# M1-Test-Board.net
KiCad netlist of a schematic drawn in Altium Designer
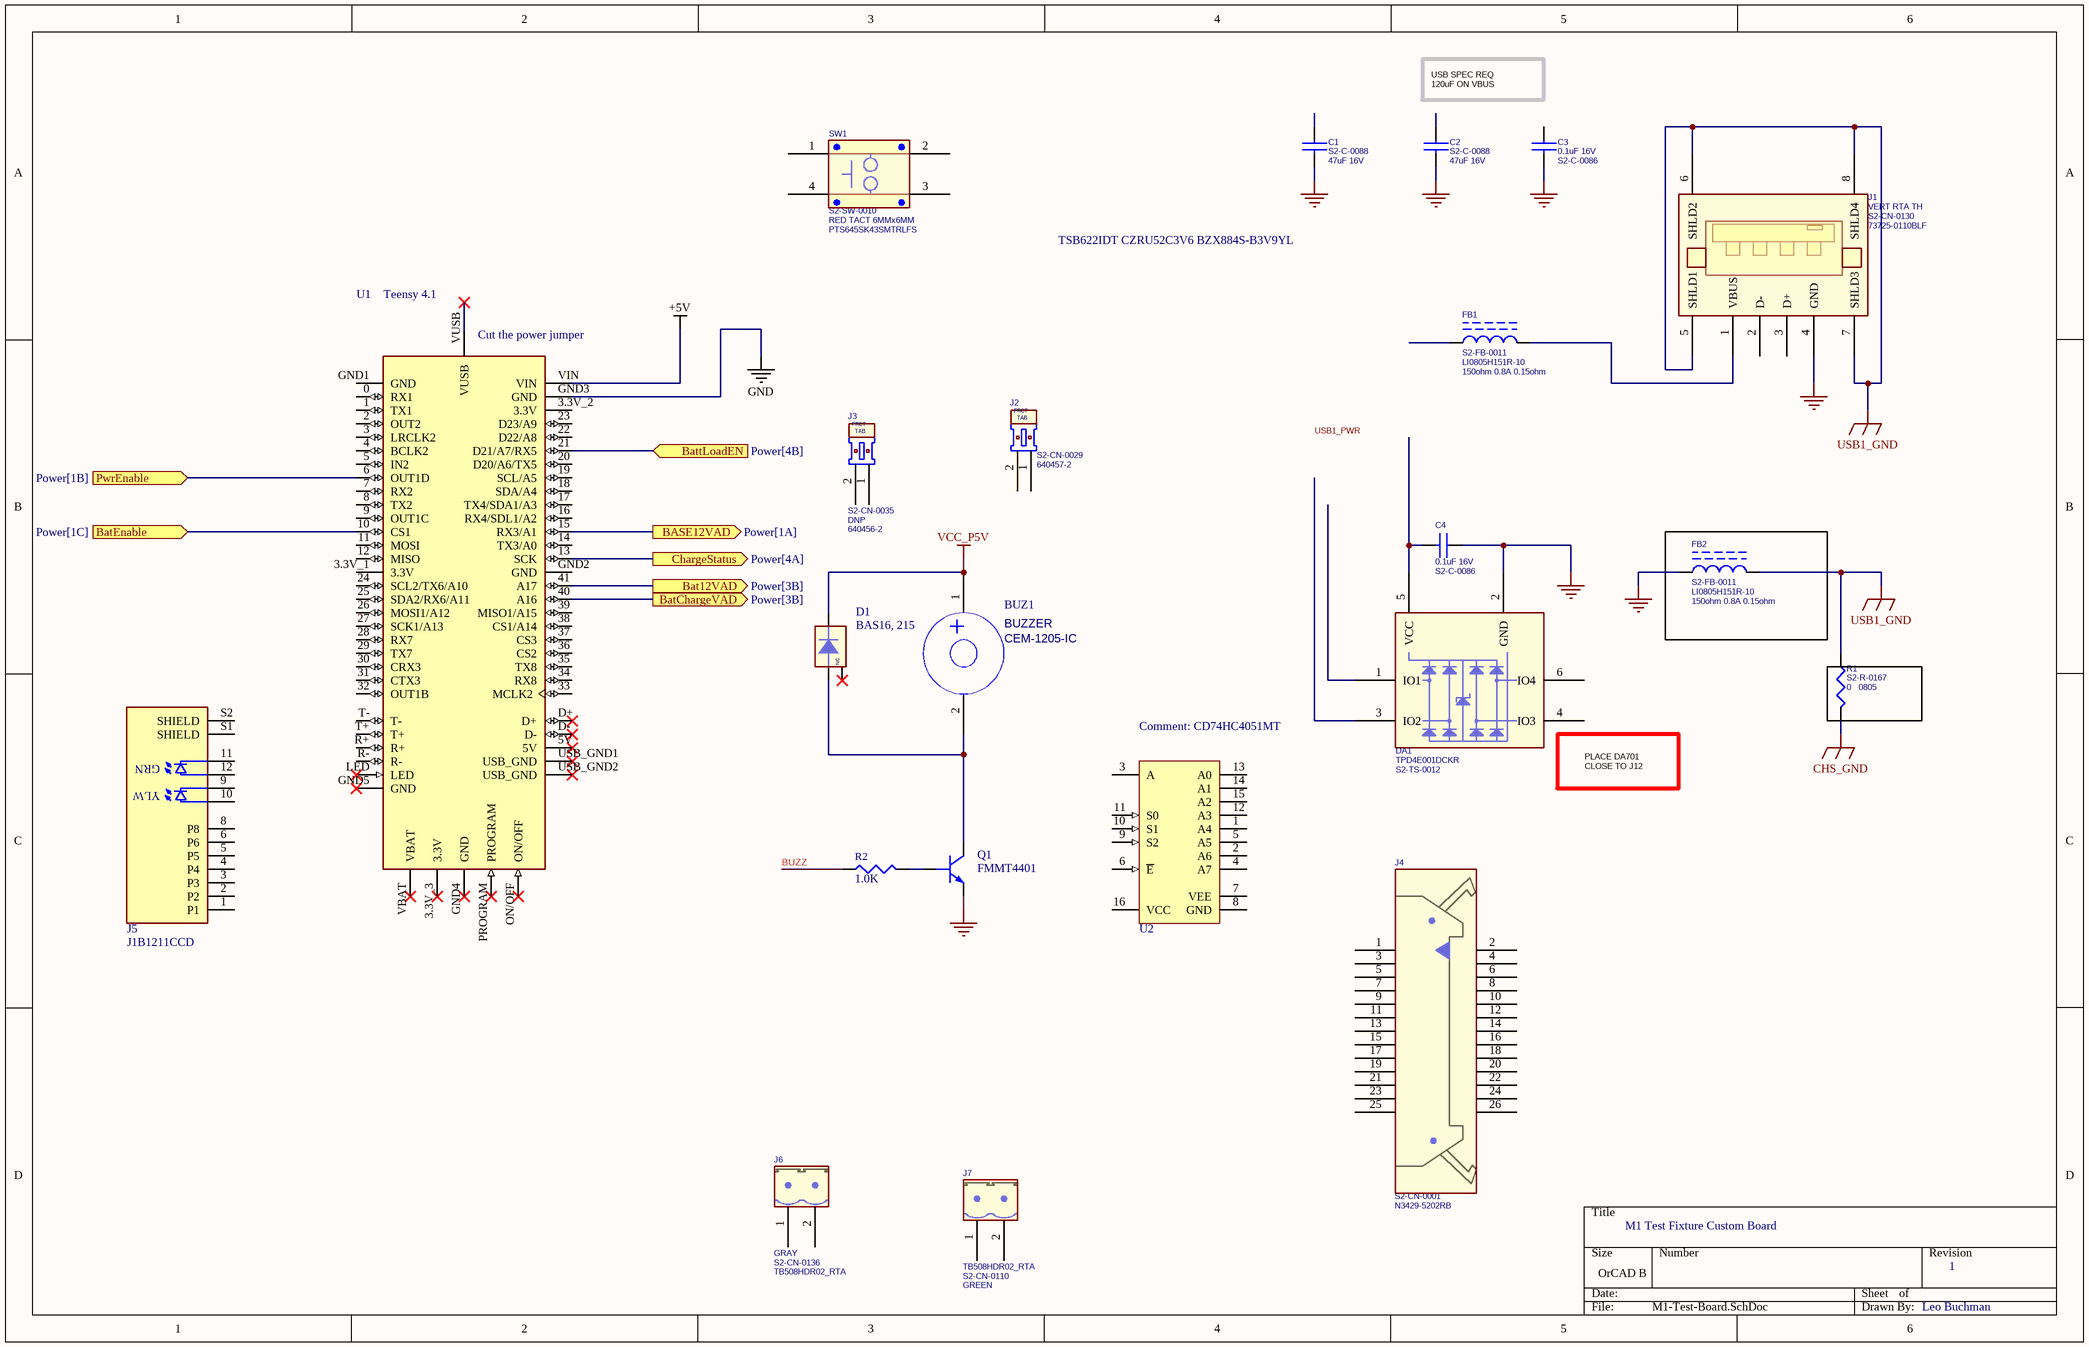
[diagram p0: M1-Test-Board.SchDoc]

(export (version "E")
  (design (tool "Eeschema 10.0.6"))
  (components
    (comp (ref "BUZ1")
      (value "BUZZER")
      (footprint "BUZZ-MB5120C")
      (description "BUZZER MAGNETIC INDICATOR, INTERNAL DRIVE 2.3KHz 12MM DIAMETER 7.6MM LEAD SPACING")
      (fields
        (field (name "PACKAGE") "CEM-1205-IC")
        (field (name "ADI PART NUMBER") "3716-0001")
        (field (name "VOLTAGE") "5V")
      )
      (libsource (lib "SAM_REV_D") (part "S2-BZ-0001"))
    )
    (comp (ref "C1")
      (value "C_47U_16V_1210")
      (footprint "CAPC3225X270N")
      (fields (field (name "S2_PN") "S2-C-0088") (field (name "DESC") "47uF 16V"))
      (libsource (lib "NODE_V2") (part "C_47U_16V_1210"))
    )
    (comp (ref "C2")
      (value "C_47U_16V_1210")
      (footprint "CAPC3225X270N")
      (fields (field (name "S2_PN") "S2-C-0088") (field (name "DESC") "47uF 16V"))
      (libsource (lib "NODE_V2") (part "C_47U_16V_1210"))
    )
    (comp (ref "C3")
      (value "C_0U1_16V_0402")
      (footprint "CAPC1005X55N")
      (fields (field (name "DESC") "0.1uF 16V") (field (name "S2_PN") "S2-C-0086"))
      (libsource (lib "NODE_V2") (part "C_0U1_16V_0402"))
    )
    (comp (ref "C4")
      (value "C_0U1_16V_0402")
      (footprint "CAPC1005X55N")
      (fields (field (name "DESC") "0.1uF 16V") (field (name "S2_PN") "S2-C-0086"))
      (libsource (lib "NODE_V2") (part "C_0U1_16V_0402"))
    )
    (comp (ref "D1")
      (value "BAS16, 215")
      (footprint "SAM_REV_D:SOT23-3")
      (description "DIODE SWITCHING 500nA REVERSE LEAKAGE SOT-23-3")
      (fields (field (name "JLCPCB_PART") "C79997"))
      (libsource (lib "SAM_REV_D") (part "S2-D-0024"))
    )
    (comp (ref "DA1")
      (value "DA_TPD4E001_ESD_QUAD")
      (footprint "SOIC65Px210X110P-6N")
      (fields (field (name "DESC") "TPD4E001DCKR") (field (name "S2_PN") "S2-TS-0012"))
      (libsource (lib "NODE_V2") (part "DA_TPD4E001_ESD_QUAD"))
    )
    (comp (ref "FB1")
      (value "FB_0A8_150OHM_0805_DC_150mOHM")
      (footprint "FB0805")
      (fields
        (field (name "S2_PN") "S2-FB-0011")
        (field (name "DESC") "LI0805H151R-10")
        (field (name "ATTR2") "150ohm 0.8A 0.15ohm")
      )
      (libsource (lib "NODE_V2") (part "FB_0A8_150OHM_0805_DC_150mOHM"))
    )
    (comp (ref "FB2")
      (value "FB_0A8_150OHM_0805_DC_150mOHM")
      (footprint "FB0805")
      (fields
        (field (name "S2_PN") "S2-FB-0011")
        (field (name "DESC") "LI0805H151R-10")
        (field (name "ATTR2") "150ohm 0.8A 0.15ohm")
      )
      (libsource (lib "NODE_V2") (part "FB_0A8_150OHM_0805_DC_150mOHM"))
    )
    (comp (ref "J1")
      (value "CN_USB_TYPE_A_RTA_VERT_TH")
      (footprint "CONN_73725-0110BLF")
      (fields
        (field (name "ATTR2") "VERT RTA TH")
        (field (name "S2_PN") "S2-CN-0130")
        (field (name "DESC") "73725-0110BLF")
      )
      (libsource (lib "NODE_V2_M1") (part "CN_USB_TYPE_A_RTA_VERT_TH"))
    )
    (comp (ref "J2")
      (value "CN_100_2POS_RTA_FRICT_LOCK")
      (footprint "CONN_640457-2")
      (fields (field (name "S2_PN") "S2-CN-0029") (field (name "DESC") "640457-2"))
      (libsource (lib "NODE_V2_M1") (part "CN_100_2POS_RTA_FRICT_LOCK"))
    )
    (comp (ref "J3")
      (value "CN_100_2POS_STR_FRICT_LOCK")
      (footprint "Conn_640456-2")
      (fields (field (name "S2_PN") "S2-CN-0035") (field (name "DNP") "DNP") (field (name "DESC") "640456-2"))
      (libsource (lib "NODE_V2_M1") (part "CN_100_2POS_STR_FRICT_LOCK"))
    )
    (comp (ref "J4")
      (value "CN_100_26POS_13x2_RTA_LATCH")
      (footprint "CONN_N3429-5202RB")
      (fields (field (name "S2_PN") "S2-CN-0001") (field (name "DESC") "N3429-5202RB"))
      (libsource (lib "NODE_V2_M1") (part "CN_100_26POS_13x2_RTA_LATCH"))
    )
    (comp (ref "J5")
      (value "J1B1211CCD")
      (footprint "RJ45-TH_J1B1211CCD-EasyEda")
      (description "Single RJ45 Connector Module with 10/100 BASE")
      (fields (field (name "MANUFACTURER") "WIZnet") (field (name "LCSC PART NUMBER") "C910371"))
      (libsource (lib "Leo-Home-SQL-Lib") (part "SI-60182-F"))
    )
    (comp (ref "J6")
      (value "CN_5MM08_02POS_HEADER_RTA_GRAY")
      (footprint "Conn_5433668")
      (fields
        (field (name "ATTR2") "GRAY")
        (field (name "S2_PN") "S2-CN-0136")
        (field (name "DESC") "TB508HDR02_RTA")
      )
      (libsource (lib "NODE_V2_M1") (part "CN_5MM08_02POS_HEADER_RTA_GRAY"))
    )
    (comp (ref "J7")
      (value "CN_5MM08_02POS_HEADER_RTA_GRN")
      (footprint "Conn_5442002")
      (fields
        (field (name "DESC") "TB508HDR02_RTA")
        (field (name "S2_PN") "S2-CN-0110")
        (field (name "ATTR2") "GREEN")
      )
      (libsource (lib "NODE_V2_M1") (part "CN_5MM08_02POS_HEADER_RTA_GRN"))
    )
    (comp (ref "Q1")
      (value "FMMT4401")
      (footprint "SOT23-3")
      (description "TRANSISTOR NPN GEN PUR SOT-23")
      (fields (field (name "JLCPCB_PART") "C20526"))
      (libsource (lib "SAM_REV_D") (part "S2-Q-0005"))
    )
    (comp (ref "R1")
      (value "R_0_0805")
      (footprint "RESC2012X50N")
      (fields (field (name "S2_PN") "S2-R-0167") (field (name "DESC") "0   0805"))
      (libsource (lib "NODE_V2") (part "R_0_0805"))
    )
    (comp (ref "R2")
      (value "1.0K")
      (footprint "r0402")
      (description "RES 1K OHM 1/16W 1% 0402")
      (fields (field (name "JLCPCB_PART") "C21190"))
      (libsource (lib "SAM_REV_D") (part "S2-R-0157"))
    )
    (comp (ref "SW1")
      (value "SW_PTS645_SMT_RED")
      (footprint "SW_PTS645SK43SMTRLFS")
      (fields
        (field (name "S2_PN") "S2-SW-0010")
        (field (name "ATTR") "RED TACT 6MMx6MM")
        (field (name "DESC") "PTS645SK43SMTRLFS")
      )
      (libsource (lib "NODE_V2_M1") (part "SW_PTS645_SMT_RED"))
    )
    (comp (ref "U1")
      (value "Teensy 4.1")
      (footprint "MODULE_DEV-16771")
      (description "RT1062 Teensy 4.1 series ARM® Cortex®-M7 MPU")
      (fields (field (name "MANUFACTURER") "SparkFun") (field (name "MANUFACTURER PART NUMBER") "16771"))
      (libsource (lib "Leo-Home-SQL-Lib") (part "DEV-16771"))
    )
    (comp (ref "U2")
      (value "CD74HC4051MT")
      (footprint "D0016A_N")
      (description "High Speed CMOS 8-Channel Analog Multiplexer/Demultiplexer, D0016A, SMALL T&R")
      (fields
        (field (name "GENERIC PART NUMBER") "CD74HC4051")
        (field (name "MANUFACTURER") "Texas Instruments")
      )
      (libsource (lib "Altium Content Vault") (part "TI-CD74HCX4051-16"))
    )
  )
  (nets
    (net (code "1") (name "+5V") (class "Default")
      (node (ref "U1") (pin "VIN") (pinfunction "VIN_VIN") (pintype "power_in"))
    )
    (net (code "2") (name "/BASE12VAD") (class "Default")
      (node (ref "U1") (pin "15") (pinfunction "RX3/A1_15") (pintype "bidirectional"))
    )
    (net (code "3") (name "/BUZZ") (class "Default")
      (node (ref "R2") (pin "1") (pinfunction "1_1") (pintype "passive"))
    )
    (net (code "4") (name "/Bat12VAD") (class "Default")
      (node (ref "U1") (pin "41") (pinfunction "A17_41") (pintype "bidirectional"))
    )
    (net (code "5") (name "/BatChargeVAD") (class "Default")
      (node (ref "U1") (pin "40") (pinfunction "A16_40") (pintype "bidirectional"))
    )
    (net (code "6") (name "/BatEnable") (class "Default")
      (node (ref "U1") (pin "10") (pinfunction "CS1_10") (pintype "bidirectional"))
    )
    (net (code "7") (name "/BattLoadEN") (class "Default")
      (node (ref "U1") (pin "21") (pinfunction "D21/A7/RX5_21") (pintype "bidirectional"))
    )
    (net (code "8") (name "/ChargeStatus") (class "Default")
      (node (ref "U1") (pin "13") (pinfunction "SCK_13") (pintype "bidirectional"))
    )
    (net (code "9") (name "/PwrEnable") (class "Default")
      (node (ref "U1") (pin "6") (pinfunction "OUT1D_6") (pintype "bidirectional"))
    )
    (net (code "11") (name "CHS_GND") (class "Default")
      (node (ref "R1") (pin "2") (pinfunction "2_2") (pintype "passive"))
    )
    (net (code "12") (name "GND") (class "Default")
      (node (ref "C1") (pin "2") (pinfunction "2_2") (pintype "passive"))
      (node (ref "C2") (pin "2") (pinfunction "2_2") (pintype "passive"))
      (node (ref "C3") (pin "2") (pinfunction "2_2") (pintype "passive"))
      (node (ref "C4") (pin "1") (pinfunction "1_1") (pintype "passive"))
      (node (ref "DA1") (pin "2") (pinfunction "GND_2") (pintype "passive"))
      (node (ref "FB2") (pin "1") (pinfunction "1_1") (pintype "passive"))
      (node (ref "J1") (pin "4") (pinfunction "GND_4") (pintype "passive"))
      (node (ref "Q1") (pin "2") (pinfunction "E_2") (pintype "passive"))
      (node (ref "U1") (pin "GND3") (pinfunction "GND_GND3") (pintype "power_in"))
    )
    (net (code "13") (name "Net-(BUZ1-NEG)") (class "Default")
      (node (ref "BUZ1") (pin "2") (pinfunction "NEG_2") (pintype "power_in"))
      (node (ref "D1") (pin "1") (pinfunction "A_1") (pintype "passive"))
      (node (ref "Q1") (pin "1") (pinfunction "C_1") (pintype "passive"))
    )
    (net (code "14") (name "Net-(DA1-VCC)") (class "Default")
      (node (ref "C4") (pin "2") (pinfunction "2_2") (pintype "passive"))
      (node (ref "DA1") (pin "5") (pinfunction "VCC_5") (pintype "passive"))
    )
    (net (code "15") (name "Net-(J1-VBUS)") (class "Default")
      (node (ref "FB1") (pin "2") (pinfunction "2_2") (pintype "passive"))
      (node (ref "J1") (pin "1") (pinfunction "VBUS_1") (pintype "passive"))
    )
    (net (code "16") (name "Net-(Q1-B)") (class "Default")
      (node (ref "Q1") (pin "3") (pinfunction "B_3") (pintype "passive"))
      (node (ref "R2") (pin "2") (pinfunction "2_2") (pintype "passive"))
    )
    (net (code "17") (name "USB1_GND") (class "Default")
      (node (ref "FB2") (pin "2") (pinfunction "2_2") (pintype "passive"))
      (node (ref "J1") (pin "5") (pinfunction "SHLD1_5") (pintype "passive"))
      (node (ref "J1") (pin "6") (pinfunction "SHLD2_6") (pintype "passive"))
      (node (ref "J1") (pin "7") (pinfunction "SHLD3_7") (pintype "passive"))
      (node (ref "J1") (pin "8") (pinfunction "SHLD4_8") (pintype "passive"))
      (node (ref "R1") (pin "1") (pinfunction "1_1") (pintype "passive"))
    )
    (net (code "18") (name "VCC_P5V") (class "Default")
      (node (ref "BUZ1") (pin "1") (pinfunction "POS_1") (pintype "power_in"))
      (node (ref "D1") (pin "3") (pinfunction "C_3") (pintype "passive"))
    )
    (net (code "19") (name "unconnected-(C1-Pad1)") (class "Default")
      (node (ref "C1") (pin "1") (pinfunction "1_1") (pintype "passive"))
    )
    (net (code "20") (name "unconnected-(C2-Pad1)") (class "Default")
      (node (ref "C2") (pin "1") (pinfunction "1_1") (pintype "passive"))
    )
    (net (code "21") (name "unconnected-(C3-Pad1)") (class "Default")
      (node (ref "C3") (pin "1") (pinfunction "1_1") (pintype "passive"))
    )
    (net (code "22") (name "unconnected-(D1-NC-Pad2)") (class "Default")
      (node (ref "D1") (pin "2") (pinfunction "NC_2") (pintype "passive+no_connect"))
    )
    (net (code "23") (name "unconnected-(DA1-IO1-Pad1)") (class "Default")
      (node (ref "DA1") (pin "1") (pinfunction "IO1_1") (pintype "passive"))
    )
    (net (code "24") (name "unconnected-(DA1-IO2-Pad3)") (class "Default")
      (node (ref "DA1") (pin "3") (pinfunction "IO2_3") (pintype "passive"))
    )
    (net (code "25") (name "unconnected-(DA1-IO3-Pad4)") (class "Default")
      (node (ref "DA1") (pin "4") (pinfunction "IO3_4") (pintype "passive"))
    )
    (net (code "26") (name "unconnected-(DA1-IO4-Pad6)") (class "Default")
      (node (ref "DA1") (pin "6") (pinfunction "IO4_6") (pintype "passive"))
    )
    (net (code "27") (name "unconnected-(FB1-Pad1)") (class "Default")
      (node (ref "FB1") (pin "1") (pinfunction "1_1") (pintype "passive"))
    )
    (net (code "28") (name "unconnected-(J1-D+-Pad3)") (class "Default")
      (node (ref "J1") (pin "3") (pinfunction "D+_3") (pintype "passive"))
    )
    (net (code "29") (name "unconnected-(J1-D--Pad2)") (class "Default")
      (node (ref "J1") (pin "2") (pinfunction "D-_2") (pintype "passive"))
    )
    (net (code "30") (name "unconnected-(J2-Pad1)") (class "Default")
      (node (ref "J2") (pin "1") (pinfunction "1_1") (pintype "passive"))
    )
    (net (code "31") (name "unconnected-(J2-Pad2)") (class "Default")
      (node (ref "J2") (pin "2") (pinfunction "2_2") (pintype "passive"))
    )
    (net (code "32") (name "unconnected-(J3-Pad1)") (class "Default")
      (node (ref "J3") (pin "1") (pinfunction "1_1") (pintype "passive"))
    )
    (net (code "33") (name "unconnected-(J3-Pad2)") (class "Default")
      (node (ref "J3") (pin "2") (pinfunction "2_2") (pintype "passive"))
    )
    (net (code "34") (name "unconnected-(J4-Pad1)") (class "Default")
      (node (ref "J4") (pin "1") (pinfunction "1_1") (pintype "passive"))
    )
    (net (code "35") (name "unconnected-(J4-Pad2)") (class "Default")
      (node (ref "J4") (pin "2") (pinfunction "2_2") (pintype "passive"))
    )
    (net (code "36") (name "unconnected-(J4-Pad3)") (class "Default")
      (node (ref "J4") (pin "3") (pinfunction "3_3") (pintype "passive"))
    )
    (net (code "37") (name "unconnected-(J4-Pad4)") (class "Default")
      (node (ref "J4") (pin "4") (pinfunction "4_4") (pintype "passive"))
    )
    (net (code "38") (name "unconnected-(J4-Pad5)") (class "Default")
      (node (ref "J4") (pin "5") (pinfunction "5_5") (pintype "passive"))
    )
    (net (code "39") (name "unconnected-(J4-Pad6)") (class "Default")
      (node (ref "J4") (pin "6") (pinfunction "6_6") (pintype "passive"))
    )
    (net (code "40") (name "unconnected-(J4-Pad7)") (class "Default")
      (node (ref "J4") (pin "7") (pinfunction "7_7") (pintype "passive"))
    )
    (net (code "41") (name "unconnected-(J4-Pad8)") (class "Default")
      (node (ref "J4") (pin "8") (pinfunction "8_8") (pintype "passive"))
    )
    (net (code "42") (name "unconnected-(J4-Pad9)") (class "Default")
      (node (ref "J4") (pin "9") (pinfunction "9_9") (pintype "passive"))
    )
    (net (code "43") (name "unconnected-(J4-Pad10)") (class "Default")
      (node (ref "J4") (pin "10") (pinfunction "10_10") (pintype "passive"))
    )
    (net (code "44") (name "unconnected-(J4-Pad11)") (class "Default")
      (node (ref "J4") (pin "11") (pinfunction "11_11") (pintype "passive"))
    )
    (net (code "45") (name "unconnected-(J4-Pad12)") (class "Default")
      (node (ref "J4") (pin "12") (pinfunction "12_12") (pintype "passive"))
    )
    (net (code "46") (name "unconnected-(J4-Pad13)") (class "Default")
      (node (ref "J4") (pin "13") (pinfunction "13_13") (pintype "passive"))
    )
    (net (code "47") (name "unconnected-(J4-Pad14)") (class "Default")
      (node (ref "J4") (pin "14") (pinfunction "14_14") (pintype "passive"))
    )
    (net (code "48") (name "unconnected-(J4-Pad15)") (class "Default")
      (node (ref "J4") (pin "15") (pinfunction "15_15") (pintype "passive"))
    )
    (net (code "49") (name "unconnected-(J4-Pad16)") (class "Default")
      (node (ref "J4") (pin "16") (pinfunction "16_16") (pintype "passive"))
    )
    (net (code "50") (name "unconnected-(J4-Pad17)") (class "Default")
      (node (ref "J4") (pin "17") (pinfunction "17_17") (pintype "passive"))
    )
    (net (code "51") (name "unconnected-(J4-Pad18)") (class "Default")
      (node (ref "J4") (pin "18") (pinfunction "18_18") (pintype "passive"))
    )
    (net (code "52") (name "unconnected-(J4-Pad19)") (class "Default")
      (node (ref "J4") (pin "19") (pinfunction "19_19") (pintype "passive"))
    )
    (net (code "53") (name "unconnected-(J4-Pad20)") (class "Default")
      (node (ref "J4") (pin "20") (pinfunction "20_20") (pintype "passive"))
    )
    (net (code "54") (name "unconnected-(J4-Pad21)") (class "Default")
      (node (ref "J4") (pin "21") (pinfunction "21_21") (pintype "passive"))
    )
    (net (code "55") (name "unconnected-(J4-Pad22)") (class "Default")
      (node (ref "J4") (pin "22") (pinfunction "22_22") (pintype "passive"))
    )
    (net (code "56") (name "unconnected-(J4-Pad23)") (class "Default")
      (node (ref "J4") (pin "23") (pinfunction "23_23") (pintype "passive"))
    )
    (net (code "57") (name "unconnected-(J4-Pad24)") (class "Default")
      (node (ref "J4") (pin "24") (pinfunction "24_24") (pintype "passive"))
    )
    (net (code "58") (name "unconnected-(J4-Pad25)") (class "Default")
      (node (ref "J4") (pin "25") (pinfunction "25_25") (pintype "passive"))
    )
    (net (code "59") (name "unconnected-(J4-Pad26)") (class "Default")
      (node (ref "J4") (pin "26") (pinfunction "26_26") (pintype "passive"))
    )
    (net (code "60") (name "unconnected-(J5-GA-Pad11)") (class "Default")
      (node (ref "J5") (pin "11") (pinfunction "GA_11") (pintype "passive"))
    )
    (net (code "61") (name "unconnected-(J5-GK-Pad12)") (class "Default")
      (node (ref "J5") (pin "12") (pinfunction "GK_12") (pintype "passive"))
    )
    (net (code "62") (name "unconnected-(J5-P1-Pad1)") (class "Default")
      (node (ref "J5") (pin "1") (pinfunction "P1_1") (pintype "passive"))
    )
    (net (code "63") (name "unconnected-(J5-P2-Pad2)") (class "Default")
      (node (ref "J5") (pin "2") (pinfunction "P2_2") (pintype "passive"))
    )
    (net (code "64") (name "unconnected-(J5-P3-Pad3)") (class "Default")
      (node (ref "J5") (pin "3") (pinfunction "P3_3") (pintype "passive"))
    )
    (net (code "65") (name "unconnected-(J5-P4-Pad4)") (class "Default")
      (node (ref "J5") (pin "4") (pinfunction "P4_4") (pintype "passive"))
    )
    (net (code "66") (name "unconnected-(J5-P5-Pad5)") (class "Default")
      (node (ref "J5") (pin "5") (pinfunction "P5_5") (pintype "passive"))
    )
    (net (code "67") (name "unconnected-(J5-P6-Pad6)") (class "Default")
      (node (ref "J5") (pin "6") (pinfunction "P6_6") (pintype "passive"))
    )
    (net (code "68") (name "unconnected-(J5-P8-Pad8)") (class "Default")
      (node (ref "J5") (pin "8") (pinfunction "P8_8") (pintype "passive"))
    )
    (net (code "69") (name "unconnected-(J5-SHIELD-PadS1)") (class "Default")
      (node (ref "J5") (pin "S1") (pinfunction "SHIELD_S1") (pintype "passive"))
    )
    (net (code "70") (name "unconnected-(J5-SHIELD-PadS2)") (class "Default")
      (node (ref "J5") (pin "S2") (pinfunction "SHIELD_S2") (pintype "passive"))
    )
    (net (code "71") (name "unconnected-(J5-YA-Pad9)") (class "Default")
      (node (ref "J5") (pin "9") (pinfunction "YA_9") (pintype "passive"))
    )
    (net (code "72") (name "unconnected-(J5-YK-Pad10)") (class "Default")
      (node (ref "J5") (pin "10") (pinfunction "YK_10") (pintype "passive"))
    )
    (net (code "73") (name "unconnected-(J6-Pad1)") (class "Default")
      (node (ref "J6") (pin "1") (pinfunction "1_1") (pintype "passive"))
    )
    (net (code "74") (name "unconnected-(J6-Pad2)") (class "Default")
      (node (ref "J6") (pin "2") (pinfunction "2_2") (pintype "passive"))
    )
    (net (code "75") (name "unconnected-(J7-Pad1)") (class "Default")
      (node (ref "J7") (pin "1") (pinfunction "1_1") (pintype "passive"))
    )
    (net (code "76") (name "unconnected-(J7-Pad2)") (class "Default")
      (node (ref "J7") (pin "2") (pinfunction "2_2") (pintype "passive"))
    )
    (net (code "77") (name "unconnected-(SW1-Pad1)") (class "Default")
      (node (ref "SW1") (pin "1") (pinfunction "1_1") (pintype "passive"))
    )
    (net (code "78") (name "unconnected-(SW1-Pad2)") (class "Default")
      (node (ref "SW1") (pin "2") (pinfunction "2_2") (pintype "passive"))
    )
    (net (code "79") (name "unconnected-(SW1-Pad3)") (class "Default")
      (node (ref "SW1") (pin "3") (pinfunction "3_3") (pintype "passive"))
    )
    (net (code "80") (name "unconnected-(SW1-Pad4)") (class "Default")
      (node (ref "SW1") (pin "4") (pinfunction "4_4") (pintype "passive"))
    )
    (net (code "81") (name "unconnected-(U1-3.3V-Pad3.3V_1)") (class "Default")
      (node (ref "U1") (pin "3.3V_1") (pinfunction "3.3V_3.3V_1") (pintype "power_in"))
    )
    (net (code "82") (name "unconnected-(U1-3.3V-Pad3.3V_2)") (class "Default")
      (node (ref "U1") (pin "3.3V_2") (pinfunction "3.3V_3.3V_2") (pintype "power_in"))
    )
    (net (code "83") (name "unconnected-(U1-3.3V-Pad3.3V_3)") (class "Default")
      (node (ref "U1") (pin "3.3V_3") (pinfunction "3.3V_3.3V_3") (pintype "power_in+no_connect"))
    )
    (net (code "84") (name "unconnected-(U1-BCLK2-Pad4)") (class "Default")
      (node (ref "U1") (pin "4") (pinfunction "BCLK2_4") (pintype "bidirectional"))
    )
    (net (code "85") (name "unconnected-(U1-CRX3-Pad30)") (class "Default")
      (node (ref "U1") (pin "30") (pinfunction "CRX3_30") (pintype "bidirectional"))
    )
    (net (code "86") (name "unconnected-(U1-CS1{slash}A14-Pad38)") (class "Default")
      (node (ref "U1") (pin "38") (pinfunction "CS1/A14_38") (pintype "bidirectional"))
    )
    (net (code "87") (name "unconnected-(U1-CS2-Pad36)") (class "Default")
      (node (ref "U1") (pin "36") (pinfunction "CS2_36") (pintype "bidirectional"))
    )
    (net (code "88") (name "unconnected-(U1-CS3-Pad37)") (class "Default")
      (node (ref "U1") (pin "37") (pinfunction "CS3_37") (pintype "bidirectional"))
    )
    (net (code "89") (name "unconnected-(U1-CTX3-Pad31)") (class "Default")
      (node (ref "U1") (pin "31") (pinfunction "CTX3_31") (pintype "bidirectional"))
    )
    (net (code "90") (name "unconnected-(U1-D20{slash}A6{slash}TX5-Pad20)") (class "Default")
      (node (ref "U1") (pin "20") (pinfunction "D20/A6/TX5_20") (pintype "bidirectional"))
    )
    (net (code "91") (name "unconnected-(U1-D22{slash}A8-Pad22)") (class "Default")
      (node (ref "U1") (pin "22") (pinfunction "D22/A8_22") (pintype "bidirectional"))
    )
    (net (code "92") (name "unconnected-(U1-D23{slash}A9-Pad23)") (class "Default")
      (node (ref "U1") (pin "23") (pinfunction "D23/A9_23") (pintype "bidirectional"))
    )
    (net (code "93") (name "unconnected-(U1-GND-PadGND1)") (class "Default")
      (node (ref "U1") (pin "GND1") (pinfunction "GND_GND1") (pintype "power_in"))
    )
    (net (code "94") (name "unconnected-(U1-GND-PadGND2)") (class "Default")
      (node (ref "U1") (pin "GND2") (pinfunction "GND_GND2") (pintype "power_in"))
    )
    (net (code "95") (name "unconnected-(U1-GND-PadGND4)") (class "Default")
      (node (ref "U1") (pin "GND4") (pinfunction "GND_GND4") (pintype "power_in+no_connect"))
    )
    (net (code "96") (name "unconnected-(U1-GND-PadGND5)") (class "Default")
      (node (ref "U1") (pin "GND5") (pinfunction "GND_GND5") (pintype "power_in+no_connect"))
    )
    (net (code "97") (name "unconnected-(U1-IN2-Pad5)") (class "Default")
      (node (ref "U1") (pin "5") (pinfunction "IN2_5") (pintype "bidirectional"))
    )
    (net (code "98") (name "unconnected-(U1-LRCLK2-Pad3)") (class "Default")
      (node (ref "U1") (pin "3") (pinfunction "LRCLK2_3") (pintype "bidirectional"))
    )
    (net (code "99") (name "unconnected-(U1-MCLK2-Pad33)") (class "Default")
      (node (ref "U1") (pin "33") (pinfunction "MCLK2_33") (pintype "bidirectional"))
    )
    (net (code "100") (name "unconnected-(U1-MISO-Pad12)") (class "Default")
      (node (ref "U1") (pin "12") (pinfunction "MISO_12") (pintype "bidirectional"))
    )
    (net (code "101") (name "unconnected-(U1-MISO1{slash}A15-Pad39)") (class "Default")
      (node (ref "U1") (pin "39") (pinfunction "MISO1/A15_39") (pintype "bidirectional"))
    )
    (net (code "102") (name "unconnected-(U1-MOSI-Pad11)") (class "Default")
      (node (ref "U1") (pin "11") (pinfunction "MOSI_11") (pintype "bidirectional"))
    )
    (net (code "103") (name "unconnected-(U1-MOSI1{slash}A12-Pad26)") (class "Default")
      (node (ref "U1") (pin "26") (pinfunction "MOSI1/A12_26") (pintype "bidirectional"))
    )
    (net (code "104") (name "unconnected-(U1-OUT1B-Pad32)") (class "Default")
      (node (ref "U1") (pin "32") (pinfunction "OUT1B_32") (pintype "bidirectional"))
    )
    (net (code "105") (name "unconnected-(U1-OUT1C-Pad9)") (class "Default")
      (node (ref "U1") (pin "9") (pinfunction "OUT1C_9") (pintype "bidirectional"))
    )
    (net (code "106") (name "unconnected-(U1-OUT2-Pad2)") (class "Default")
      (node (ref "U1") (pin "2") (pinfunction "OUT2_2") (pintype "bidirectional"))
    )
    (net (code "107") (name "unconnected-(U1-Pad5V)") (class "Default")
      (node (ref "U1") (pin "5V") (pinfunction "5V_5V") (pintype "power_in+no_connect"))
    )
    (net (code "108") (name "unconnected-(U1-PadD+)") (class "Default")
      (node (ref "U1") (pin "D+") (pinfunction "D+_D+") (pintype "bidirectional+no_connect"))
    )
    (net (code "109") (name "unconnected-(U1-PadD-)") (class "Default")
      (node (ref "U1") (pin "D-") (pinfunction "D-_D-") (pintype "bidirectional+no_connect"))
    )
    (net (code "110") (name "unconnected-(U1-PadLED)") (class "Default")
      (node (ref "U1") (pin "LED") (pinfunction "LED_LED") (pintype "input+no_connect"))
    )
    (net (code "111") (name "unconnected-(U1-PadON{slash}OFF)") (class "Default")
      (node (ref "U1") (pin "ON/OFF") (pinfunction "ON/OFF_ON/OFF") (pintype "input+no_connect"))
    )
    (net (code "112") (name "unconnected-(U1-PadPROGRAM)") (class "Default")
      (node (ref "U1") (pin "PROGRAM") (pinfunction "PROGRAM_PROGRAM") (pintype "input+no_connect"))
    )
    (net (code "113") (name "unconnected-(U1-PadR+)") (class "Default")
      (node (ref "U1") (pin "R+") (pinfunction "R+_R+") (pintype "bidirectional"))
    )
    (net (code "114") (name "unconnected-(U1-PadR-)") (class "Default")
      (node (ref "U1") (pin "R-") (pinfunction "R-_R-") (pintype "bidirectional"))
    )
    (net (code "115") (name "unconnected-(U1-PadT+)") (class "Default")
      (node (ref "U1") (pin "T+") (pinfunction "T+_T+") (pintype "bidirectional"))
    )
    (net (code "116") (name "unconnected-(U1-PadT-)") (class "Default")
      (node (ref "U1") (pin "T-") (pinfunction "T-_T-") (pintype "bidirectional"))
    )
    (net (code "117") (name "unconnected-(U1-PadVBAT)") (class "Default")
      (node (ref "U1") (pin "VBAT") (pinfunction "VBAT_VBAT") (pintype "passive+no_connect"))
    )
    (net (code "118") (name "unconnected-(U1-PadVUSB)") (class "Default")
      (node (ref "U1") (pin "VUSB") (pinfunction "VUSB_VUSB") (pintype "passive+no_connect"))
    )
    (net (code "119") (name "unconnected-(U1-RX1-Pad0)") (class "Default")
      (node (ref "U1") (pin "0") (pinfunction "RX1_0") (pintype "bidirectional"))
    )
    (net (code "120") (name "unconnected-(U1-RX2-Pad7)") (class "Default")
      (node (ref "U1") (pin "7") (pinfunction "RX2_7") (pintype "bidirectional"))
    )
    (net (code "121") (name "unconnected-(U1-RX4{slash}SDL1{slash}A2-Pad16)") (class "Default")
      (node (ref "U1") (pin "16") (pinfunction "RX4/SDL1/A2_16") (pintype "bidirectional"))
    )
    (net (code "122") (name "unconnected-(U1-RX7-Pad28)") (class "Default")
      (node (ref "U1") (pin "28") (pinfunction "RX7_28") (pintype "bidirectional"))
    )
    (net (code "123") (name "unconnected-(U1-RX8-Pad34)") (class "Default")
      (node (ref "U1") (pin "34") (pinfunction "RX8_34") (pintype "bidirectional"))
    )
    (net (code "124") (name "unconnected-(U1-SCK1{slash}A13-Pad27)") (class "Default")
      (node (ref "U1") (pin "27") (pinfunction "SCK1/A13_27") (pintype "bidirectional"))
    )
    (net (code "125") (name "unconnected-(U1-SCL2{slash}TX6{slash}A10-Pad24)") (class "Default")
      (node (ref "U1") (pin "24") (pinfunction "SCL2/TX6/A10_24") (pintype "bidirectional"))
    )
    (net (code "126") (name "unconnected-(U1-SCL{slash}A5-Pad19)") (class "Default")
      (node (ref "U1") (pin "19") (pinfunction "SCL/A5_19") (pintype "bidirectional"))
    )
    (net (code "127") (name "unconnected-(U1-SDA2{slash}RX6{slash}A11-Pad25)") (class "Default")
      (node (ref "U1") (pin "25") (pinfunction "SDA2/RX6/A11_25") (pintype "bidirectional"))
    )
    (net (code "128") (name "unconnected-(U1-SDA{slash}A4-Pad18)") (class "Default")
      (node (ref "U1") (pin "18") (pinfunction "SDA/A4_18") (pintype "bidirectional"))
    )
    (net (code "129") (name "unconnected-(U1-TX1-Pad1)") (class "Default")
      (node (ref "U1") (pin "1") (pinfunction "TX1_1") (pintype "bidirectional"))
    )
    (net (code "130") (name "unconnected-(U1-TX2-Pad8)") (class "Default")
      (node (ref "U1") (pin "8") (pinfunction "TX2_8") (pintype "bidirectional"))
    )
    (net (code "131") (name "unconnected-(U1-TX3{slash}A0-Pad14)") (class "Default")
      (node (ref "U1") (pin "14") (pinfunction "TX3/A0_14") (pintype "bidirectional"))
    )
    (net (code "132") (name "unconnected-(U1-TX4{slash}SDA1{slash}A3-Pad17)") (class "Default")
      (node (ref "U1") (pin "17") (pinfunction "TX4/SDA1/A3_17") (pintype "bidirectional"))
    )
    (net (code "133") (name "unconnected-(U1-TX7-Pad29)") (class "Default")
      (node (ref "U1") (pin "29") (pinfunction "TX7_29") (pintype "bidirectional"))
    )
    (net (code "134") (name "unconnected-(U1-TX8-Pad35)") (class "Default")
      (node (ref "U1") (pin "35") (pinfunction "TX8_35") (pintype "bidirectional"))
    )
    (net (code "135") (name "unconnected-(U1-USB_GND-PadUSB_GND1)") (class "Default")
      (node (ref "U1") (pin "USB_GND1") (pinfunction "USB_GND_USB_GND1") (pintype "power_in+no_connect"))
    )
    (net (code "136") (name "unconnected-(U1-USB_GND-PadUSB_GND2)") (class "Default")
      (node (ref "U1") (pin "USB_GND2") (pinfunction "USB_GND_USB_GND2") (pintype "power_in+no_connect"))
    )
    (net (code "137") (name "unconnected-(U2-A-Pad3)") (class "Default")
      (node (ref "U2") (pin "3") (pinfunction "A_3") (pintype "passive"))
    )
    (net (code "138") (name "unconnected-(U2-A0-Pad13)") (class "Default")
      (node (ref "U2") (pin "13") (pinfunction "A0_13") (pintype "passive"))
    )
    (net (code "139") (name "unconnected-(U2-A1-Pad14)") (class "Default")
      (node (ref "U2") (pin "14") (pinfunction "A1_14") (pintype "passive"))
    )
    (net (code "140") (name "unconnected-(U2-A2-Pad15)") (class "Default")
      (node (ref "U2") (pin "15") (pinfunction "A2_15") (pintype "passive"))
    )
    (net (code "141") (name "unconnected-(U2-A3-Pad12)") (class "Default")
      (node (ref "U2") (pin "12") (pinfunction "A3_12") (pintype "passive"))
    )
    (net (code "142") (name "unconnected-(U2-A4-Pad1)") (class "Default")
      (node (ref "U2") (pin "1") (pinfunction "A4_1") (pintype "passive"))
    )
    (net (code "143") (name "unconnected-(U2-A5-Pad5)") (class "Default")
      (node (ref "U2") (pin "5") (pinfunction "A5_5") (pintype "passive"))
    )
    (net (code "144") (name "unconnected-(U2-A6-Pad2)") (class "Default")
      (node (ref "U2") (pin "2") (pinfunction "A6_2") (pintype "passive"))
    )
    (net (code "145") (name "unconnected-(U2-A7-Pad4)") (class "Default")
      (node (ref "U2") (pin "4") (pinfunction "A7_4") (pintype "passive"))
    )
    (net (code "146") (name "unconnected-(U2-GND-Pad8)") (class "Default")
      (node (ref "U2") (pin "8") (pinfunction "GND_8") (pintype "power_in"))
    )
    (net (code "147") (name "unconnected-(U2-S0-Pad11)") (class "Default")
      (node (ref "U2") (pin "11") (pinfunction "S0_11") (pintype "input"))
    )
    (net (code "148") (name "unconnected-(U2-S1-Pad10)") (class "Default")
      (node (ref "U2") (pin "10") (pinfunction "S1_10") (pintype "input"))
    )
    (net (code "149") (name "unconnected-(U2-S2-Pad9)") (class "Default")
      (node (ref "U2") (pin "9") (pinfunction "S2_9") (pintype "input"))
    )
    (net (code "150") (name "unconnected-(U2-VCC-Pad16)") (class "Default")
      (node (ref "U2") (pin "16") (pinfunction "VCC_16") (pintype "power_in"))
    )
    (net (code "151") (name "unconnected-(U2-VEE-Pad7)") (class "Default")
      (node (ref "U2") (pin "7") (pinfunction "VEE_7") (pintype "power_in"))
    )
    (net (code "152") (name "unconnected-(U2-~{E}-Pad6)") (class "Default")
      (node (ref "U2") (pin "6") (pinfunction "~{E}_6") (pintype "input"))
    )
  )
)
